# ADC.net
KiCad netlist of a schematic drawn in Altium Designer
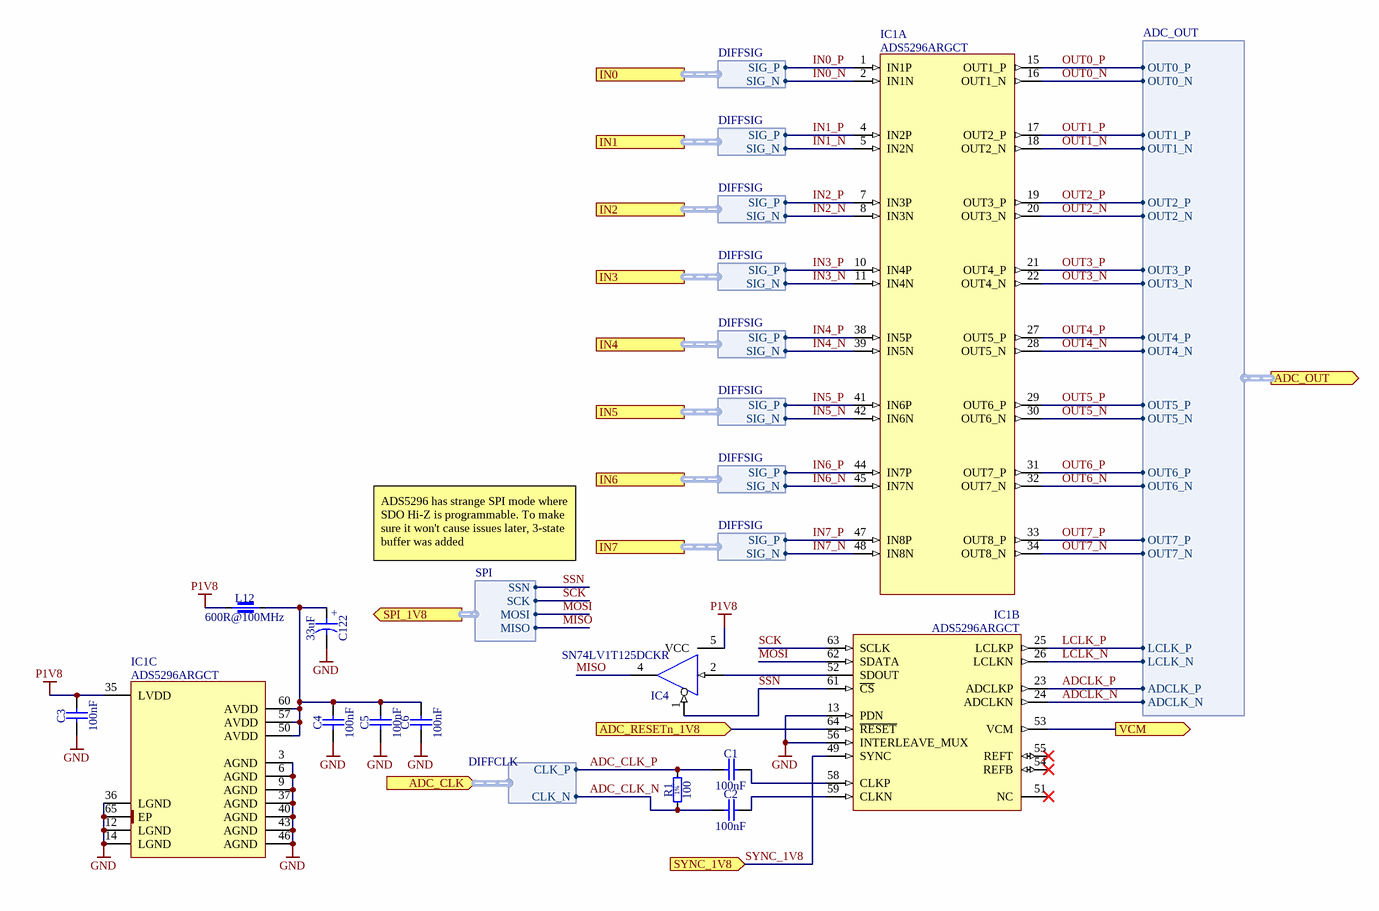
[diagram p0: ADC.SchDoc]

(export (version "E")
  (design (tool "Eeschema 10.0.6"))
  (components
    (comp (ref "C1")
      (value "100nF")
      (footprint "CAPC0603X33N")
      (description "Non-polarised capacitor")
      (fields
        (field (name "PART NUMBER") "CC0201_100NF_6.3V_10%_X5R")
        (field (name "VOLTAGE") "6.3V")
        (field (name "AUTHOR") "CERN DEM JLC")
      )
      (libsource (lib "Capacitors") (part "Capacitor - non polarized"))
    )
    (comp (ref "C2")
      (value "100nF")
      (footprint "CAPC0603X33N")
      (description "Non-polarised capacitor")
      (fields
        (field (name "PART NUMBER") "CC0201_100NF_6.3V_10%_X5R")
        (field (name "VOLTAGE") "6.3V")
        (field (name "AUTHOR") "CERN DEM JLC")
      )
      (libsource (lib "Capacitors") (part "Capacitor - non polarized"))
    )
    (comp (ref "C3")
      (value "100nF")
      (footprint "CAPC0603X33N")
      (description "Non-polarised capacitor")
      (fields
        (field (name "PART NUMBER") "CC0201_100NF_6.3V_10%_X5R")
        (field (name "VOLTAGE") "6.3V")
        (field (name "AUTHOR") "CERN DEM JLC")
      )
      (libsource (lib "Capacitors") (part "Capacitor - non polarized"))
    )
    (comp (ref "C4")
      (value "100nF")
      (footprint "CAPC0603X33N")
      (description "Non-polarised capacitor")
      (fields
        (field (name "PART NUMBER") "CC0201_100NF_6.3V_10%_X5R")
        (field (name "VOLTAGE") "6.3V")
        (field (name "AUTHOR") "CERN DEM JLC")
      )
      (libsource (lib "Capacitors") (part "Capacitor - non polarized"))
    )
    (comp (ref "C5")
      (value "100nF")
      (footprint "CAPC0603X33N")
      (description "Non-polarised capacitor")
      (fields
        (field (name "PART NUMBER") "CC0201_100NF_6.3V_10%_X5R")
        (field (name "VOLTAGE") "6.3V")
        (field (name "AUTHOR") "CERN DEM JLC")
      )
      (libsource (lib "Capacitors") (part "Capacitor - non polarized"))
    )
    (comp (ref "C6")
      (value "100nF")
      (footprint "CAPC0603X33N")
      (description "Non-polarised capacitor")
      (fields
        (field (name "PART NUMBER") "CC0201_100NF_6.3V_10%_X5R")
        (field (name "VOLTAGE") "6.3V")
        (field (name "AUTHOR") "CERN DEM JLC")
      )
      (libsource (lib "Capacitors") (part "Capacitor - non polarized"))
    )
    (comp (ref "C122")
      (value "33uF")
      (footprint "CAPMP3216X180N")
      (description "Polarised capacitor")
      (fields
        (field (name "PART NUMBER") "CTE3216-18_33UF_4V_10%")
        (field (name "VOLTAGE") "4V")
        (field (name "AUTHOR") "CERN DEM JLC")
      )
      (libsource (lib "Capacitors") (part "Capacitor - polarized"))
    )
    (comp (ref "IC1")
      (value "ADS5296ARGCT")
      (footprint "QFN50P900X900X100-65N-S725")
      (fields (field (name "MANUFACTURER") "TEXAS INSTRUMENTS") (field (name "AUTHOR") "GK"))
      (libsource (lib "LIBRARY_SCH") (part "ADC_ADS5296A"))
    )
    (comp (ref "IC4")
      (value "SN74LV1T125DCKR")
      (footprint "SOT65P210X110-5N")
      (description "Single Power Supply Single Buffer Gate with 3-State Output CMOS Logic Level Shifter")
      (fields (field (name "MANUFACTURER") "TEXAS INSTRUMENTS") (field (name "AUTHOR") "CERN DEM JLC"))
      (libsource (lib "ICs And Semiconductors") (part "741T125"))
    )
    (comp (ref "L12")
      (value "600R@100MHz")
      (footprint "INDC1005X55N")
      (fields
        (field (name "PART NUMBER") "IND0402_MURATA_BLM15HD601SN1")
        (field (name "POWER") "300mA")
        (field (name "TOLERANCE") "±25%")
        (field (name "AUTHOR") "CERN DEM JLC")
      )
      (libsource (lib "Inductors & Transformers") (part "Ferrite Bead"))
    )
    (comp (ref "R1")
      (value "100")
      (footprint "RESC0603X28N")
      (description "Resistor - 1%")
      (fields
        (field (name "PART NUMBER") "R0201_100R_1%_0.05W_200PPM")
        (field (name "POWER") "0.05W")
        (field (name "AUTHOR") "CERN DEM JLC")
      )
      (libsource (lib "Resistors") (part "Resistor - 1%"))
    )
  )
  (nets
    (net (code "5") (name "/ADCLK_N") (class "Default")
      (node (ref "IC1") (pin "24") (pinfunction "ADCLKN_24") (pintype "output"))
    )
    (net (code "6") (name "/ADCLK_P") (class "Default")
      (node (ref "IC1") (pin "23") (pinfunction "ADCLKP_23") (pintype "output"))
    )
    (net (code "7") (name "/ADC_CLK_N") (class "Default")
      (node (ref "C2") (pin "1") (pinfunction "1_1") (pintype "passive"))
      (node (ref "R1") (pin "1") (pinfunction "1_1") (pintype "passive"))
    )
    (net (code "8") (name "/ADC_CLK_P") (class "Default")
      (node (ref "C1") (pin "1") (pinfunction "1_1") (pintype "passive"))
      (node (ref "R1") (pin "2") (pinfunction "2_2") (pintype "passive"))
    )
    (net (code "9") (name "/ADC_RESETn_1V8") (class "Default")
      (node (ref "IC1") (pin "64") (pinfunction "~{RESET}_64") (pintype "input"))
    )
    (net (code "10") (name "/IN0_N") (class "Default")
      (node (ref "IC1") (pin "2") (pinfunction "IN1N_2") (pintype "input"))
    )
    (net (code "11") (name "/IN0_P") (class "Default")
      (node (ref "IC1") (pin "1") (pinfunction "IN1P_1") (pintype "input"))
    )
    (net (code "12") (name "/IN1_N") (class "Default")
      (node (ref "IC1") (pin "5") (pinfunction "IN2N_5") (pintype "input"))
    )
    (net (code "13") (name "/IN1_P") (class "Default")
      (node (ref "IC1") (pin "4") (pinfunction "IN2P_4") (pintype "input"))
    )
    (net (code "14") (name "/IN2_N") (class "Default")
      (node (ref "IC1") (pin "8") (pinfunction "IN3N_8") (pintype "input"))
    )
    (net (code "15") (name "/IN2_P") (class "Default")
      (node (ref "IC1") (pin "7") (pinfunction "IN3P_7") (pintype "input"))
    )
    (net (code "16") (name "/IN3_N") (class "Default")
      (node (ref "IC1") (pin "11") (pinfunction "IN4N_11") (pintype "input"))
    )
    (net (code "17") (name "/IN3_P") (class "Default")
      (node (ref "IC1") (pin "10") (pinfunction "IN4P_10") (pintype "input"))
    )
    (net (code "18") (name "/IN4_N") (class "Default")
      (node (ref "IC1") (pin "39") (pinfunction "IN5N_39") (pintype "input"))
    )
    (net (code "19") (name "/IN4_P") (class "Default")
      (node (ref "IC1") (pin "38") (pinfunction "IN5P_38") (pintype "input"))
    )
    (net (code "20") (name "/IN5_N") (class "Default")
      (node (ref "IC1") (pin "42") (pinfunction "IN6N_42") (pintype "input"))
    )
    (net (code "21") (name "/IN5_P") (class "Default")
      (node (ref "IC1") (pin "41") (pinfunction "IN6P_41") (pintype "input"))
    )
    (net (code "22") (name "/IN6_N") (class "Default")
      (node (ref "IC1") (pin "45") (pinfunction "IN7N_45") (pintype "input"))
    )
    (net (code "23") (name "/IN6_P") (class "Default")
      (node (ref "IC1") (pin "44") (pinfunction "IN7P_44") (pintype "input"))
    )
    (net (code "24") (name "/IN7_N") (class "Default")
      (node (ref "IC1") (pin "48") (pinfunction "IN8N_48") (pintype "input"))
    )
    (net (code "25") (name "/IN7_P") (class "Default")
      (node (ref "IC1") (pin "47") (pinfunction "IN8P_47") (pintype "input"))
    )
    (net (code "26") (name "/LCLK_N") (class "Default")
      (node (ref "IC1") (pin "26") (pinfunction "LCLKN_26") (pintype "output"))
    )
    (net (code "27") (name "/LCLK_P") (class "Default")
      (node (ref "IC1") (pin "25") (pinfunction "LCLKP_25") (pintype "output"))
    )
    (net (code "28") (name "/MISO") (class "Default")
      (node (ref "IC4") (pin "4") (pinfunction "OUT_4") (pintype "tri_state"))
    )
    (net (code "29") (name "/MOSI") (class "Default")
      (node (ref "IC1") (pin "62") (pinfunction "SDATA_62") (pintype "input"))
    )
    (net (code "30") (name "/OUT0_N") (class "Default")
      (node (ref "IC1") (pin "16") (pinfunction "OUT1_N_16") (pintype "output"))
    )
    (net (code "31") (name "/OUT0_P") (class "Default")
      (node (ref "IC1") (pin "15") (pinfunction "OUT1_P_15") (pintype "output"))
    )
    (net (code "32") (name "/OUT1_N") (class "Default")
      (node (ref "IC1") (pin "18") (pinfunction "OUT2_N_18") (pintype "output"))
    )
    (net (code "33") (name "/OUT1_P") (class "Default")
      (node (ref "IC1") (pin "17") (pinfunction "OUT2_P_17") (pintype "output"))
    )
    (net (code "34") (name "/OUT2_N") (class "Default")
      (node (ref "IC1") (pin "20") (pinfunction "OUT3_N_20") (pintype "output"))
    )
    (net (code "35") (name "/OUT2_P") (class "Default")
      (node (ref "IC1") (pin "19") (pinfunction "OUT3_P_19") (pintype "output"))
    )
    (net (code "36") (name "/OUT3_N") (class "Default")
      (node (ref "IC1") (pin "22") (pinfunction "OUT4_N_22") (pintype "output"))
    )
    (net (code "37") (name "/OUT3_P") (class "Default")
      (node (ref "IC1") (pin "21") (pinfunction "OUT4_P_21") (pintype "output"))
    )
    (net (code "38") (name "/OUT4_N") (class "Default")
      (node (ref "IC1") (pin "28") (pinfunction "OUT5_N_28") (pintype "output"))
    )
    (net (code "39") (name "/OUT4_P") (class "Default")
      (node (ref "IC1") (pin "27") (pinfunction "OUT5_P_27") (pintype "output"))
    )
    (net (code "40") (name "/OUT5_N") (class "Default")
      (node (ref "IC1") (pin "30") (pinfunction "OUT6_N_30") (pintype "output"))
    )
    (net (code "41") (name "/OUT5_P") (class "Default")
      (node (ref "IC1") (pin "29") (pinfunction "OUT6_P_29") (pintype "output"))
    )
    (net (code "42") (name "/OUT6_N") (class "Default")
      (node (ref "IC1") (pin "32") (pinfunction "OUT7_N_32") (pintype "output"))
    )
    (net (code "43") (name "/OUT6_P") (class "Default")
      (node (ref "IC1") (pin "31") (pinfunction "OUT7_P_31") (pintype "output"))
    )
    (net (code "44") (name "/OUT7_N") (class "Default")
      (node (ref "IC1") (pin "34") (pinfunction "OUT8_N_34") (pintype "output"))
    )
    (net (code "45") (name "/OUT7_P") (class "Default")
      (node (ref "IC1") (pin "33") (pinfunction "OUT8_P_33") (pintype "output"))
    )
    (net (code "46") (name "/SCK") (class "Default")
      (node (ref "IC1") (pin "63") (pinfunction "SCLK_63") (pintype "input"))
    )
    (net (code "47") (name "/SSN") (class "Default")
      (node (ref "IC1") (pin "61") (pinfunction "~{CS}_61") (pintype "input"))
      (node (ref "IC4") (pin "1") (pinfunction "~{G}_1") (pintype "input"))
    )
    (net (code "48") (name "/SYNC_1V8") (class "Default")
      (node (ref "IC1") (pin "49") (pinfunction "SYNC_49") (pintype "input"))
    )
    (net (code "49") (name "/VCM") (class "Default")
      (node (ref "IC1") (pin "53") (pinfunction "VCM_53") (pintype "output"))
    )
    (net (code "54") (name "GND") (class "Default")
      (node (ref "C122") (pin "2") (pinfunction "2_2") (pintype "passive"))
      (node (ref "C3") (pin "1") (pinfunction "1_1") (pintype "passive"))
      (node (ref "C4") (pin "1") (pinfunction "1_1") (pintype "passive"))
      (node (ref "C5") (pin "1") (pinfunction "1_1") (pintype "passive"))
      (node (ref "C6") (pin "1") (pinfunction "1_1") (pintype "passive"))
      (node (ref "IC1") (pin "12") (pinfunction "LGND_12") (pintype "power_in"))
      (node (ref "IC1") (pin "13") (pinfunction "PDN_13") (pintype "input"))
      (node (ref "IC1") (pin "14") (pinfunction "LGND_14") (pintype "power_in"))
      (node (ref "IC1") (pin "3") (pinfunction "AGND_3") (pintype "power_in"))
      (node (ref "IC1") (pin "36") (pinfunction "LGND_36") (pintype "power_in"))
      (node (ref "IC1") (pin "37") (pinfunction "AGND_37") (pintype "power_in"))
      (node (ref "IC1") (pin "40") (pinfunction "AGND_40") (pintype "power_in"))
      (node (ref "IC1") (pin "43") (pinfunction "AGND_43") (pintype "power_in"))
      (node (ref "IC1") (pin "46") (pinfunction "AGND_46") (pintype "power_in"))
      (node (ref "IC1") (pin "56") (pinfunction "INTERLEAVE_MUX_56") (pintype "input"))
      (node (ref "IC1") (pin "6") (pinfunction "AGND_6") (pintype "power_in"))
      (node (ref "IC1") (pin "65") (pinfunction "EP_65") (pintype "power_in"))
      (node (ref "IC1") (pin "9") (pinfunction "AGND_9") (pintype "power_in"))
      (node (ref "IC4") (pin "3") (pinfunction "GND_3") (pintype "power_in"))
    )
    (net (code "55") (name "Net-(C122-Pad1)") (class "Default")
      (node (ref "C122") (pin "1") (pinfunction "1_1") (pintype "passive"))
      (node (ref "C4") (pin "2") (pinfunction "2_2") (pintype "passive"))
      (node (ref "C5") (pin "2") (pinfunction "2_2") (pintype "passive"))
      (node (ref "C6") (pin "2") (pinfunction "2_2") (pintype "passive"))
      (node (ref "IC1") (pin "50") (pinfunction "AVDD_50") (pintype "power_in"))
      (node (ref "IC1") (pin "57") (pinfunction "AVDD_57") (pintype "power_in"))
      (node (ref "IC1") (pin "60") (pinfunction "AVDD_60") (pintype "power_in"))
      (node (ref "L12") (pin "2") (pinfunction "2_2") (pintype "passive"))
    )
    (net (code "56") (name "Net-(IC1B-CLKN)") (class "Default")
      (node (ref "C2") (pin "2") (pinfunction "2_2") (pintype "passive"))
      (node (ref "IC1") (pin "59") (pinfunction "CLKN_59") (pintype "input"))
    )
    (net (code "57") (name "Net-(IC1B-CLKP)") (class "Default")
      (node (ref "C1") (pin "2") (pinfunction "2_2") (pintype "passive"))
      (node (ref "IC1") (pin "58") (pinfunction "CLKP_58") (pintype "input"))
    )
    (net (code "58") (name "Net-(IC1B-SDOUT)") (class "Default")
      (node (ref "IC1") (pin "52") (pinfunction "SDOUT_52") (pintype "tri_state"))
      (node (ref "IC4") (pin "2") (pinfunction "IN_2") (pintype "input"))
    )
    (net (code "59") (name "P1V8") (class "Default")
      (node (ref "C3") (pin "2") (pinfunction "2_2") (pintype "passive"))
      (node (ref "IC1") (pin "35") (pinfunction "LVDD_35") (pintype "power_in"))
      (node (ref "IC4") (pin "5") (pinfunction "VCC_5") (pintype "power_in"))
      (node (ref "L12") (pin "1") (pinfunction "1_1") (pintype "passive"))
    )
    (net (code "60") (name "unconnected-(IC1B-NC-Pad51)") (class "Default")
      (node (ref "IC1") (pin "51") (pinfunction "NC_51") (pintype "passive+no_connect"))
    )
    (net (code "61") (name "unconnected-(IC1B-REFB-Pad54)") (class "Default")
      (node (ref "IC1") (pin "54") (pinfunction "REFB_54") (pintype "bidirectional+no_connect"))
    )
    (net (code "62") (name "unconnected-(IC1B-REFT-Pad55)") (class "Default")
      (node (ref "IC1") (pin "55") (pinfunction "REFT_55") (pintype "bidirectional+no_connect"))
    )
  )
)
